# Cypress.net
KiCad netlist of a schematic drawn in Altium Designer
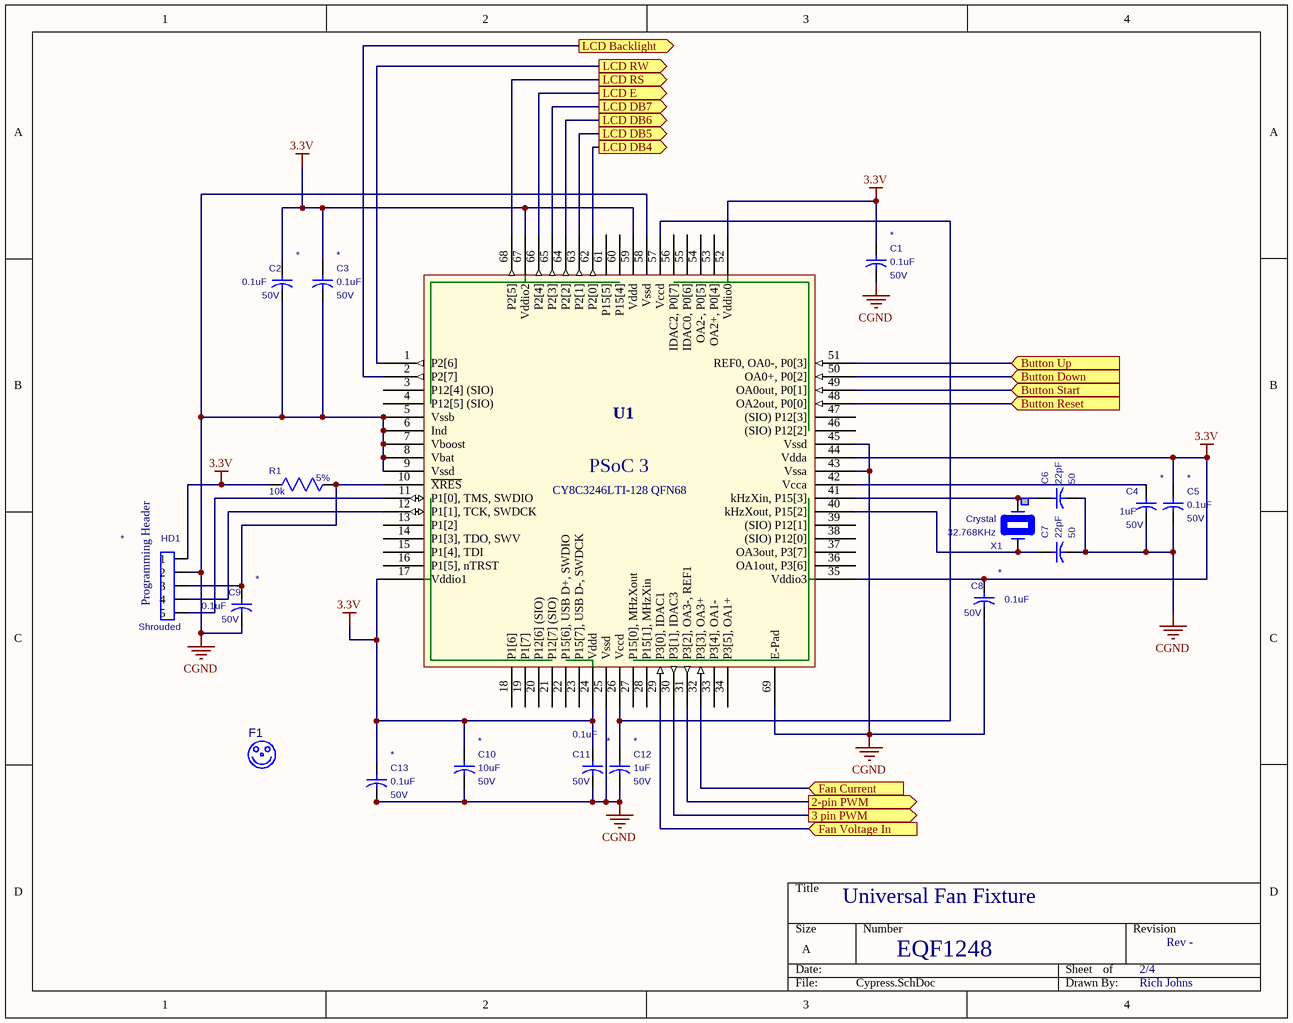
[diagram p0: Cypress.SchDoc]

(export (version "E")
  (design (tool "Eeschema 10.0.6"))
  (components
    (comp (ref "C1")
      (value "0.1uF")
      (footprint "0603")
      (fields
        (field (name "DNS") "*")
        (field (name "VOLTAGE") "50V")
        (field (name "TOLERANCE") "+/- 20%")
        (field (name "Comment") "CAP_NON_POLAR_SMT")
        (field (name "CHECKEDBY") "Sam Rhoufiry")
        (field (name "CREATEDBY") "Mike Tyger")
        (field (name "LASTUPDATEDBY") "Mike Tyger")
      )
      (libsource (lib "bome") (part "CAP_NON_POLAR_SMT"))
    )
    (comp (ref "C2")
      (value "0.1uF")
      (footprint "0603")
      (fields
        (field (name "DNS") "*")
        (field (name "VOLTAGE") "50V")
        (field (name "TOLERANCE") "+/- 20%")
        (field (name "Comment") "CAP_NON_POLAR_SMT")
        (field (name "CHECKEDBY") "Sam Rhoufiry")
        (field (name "CREATEDBY") "Mike Tyger")
        (field (name "LASTUPDATEDBY") "Mike Tyger")
      )
      (libsource (lib "bome") (part "CAP_NON_POLAR_SMT"))
    )
    (comp (ref "C3")
      (value "0.1uF")
      (footprint "0603")
      (fields
        (field (name "DNS") "*")
        (field (name "VOLTAGE") "50V")
        (field (name "TOLERANCE") "+/- 20%")
        (field (name "Comment") "CAP_NON_POLAR_SMT")
        (field (name "CHECKEDBY") "Sam Rhoufiry")
        (field (name "CREATEDBY") "Mike Tyger")
        (field (name "LASTUPDATEDBY") "Mike Tyger")
      )
      (libsource (lib "bome") (part "CAP_NON_POLAR_SMT"))
    )
    (comp (ref "C4")
      (value "1uF")
      (footprint "0603")
      (fields
        (field (name "DNS") "*")
        (field (name "VOLTAGE") "50V")
        (field (name "TOLERANCE") "+/- 20%")
        (field (name "Comment") "CAP_NON_POLAR_SMT")
        (field (name "CHECKEDBY") "Sam Rhoufiry")
        (field (name "CREATEDBY") "Mike Tyger")
        (field (name "LASTUPDATEDBY") "Mike Tyger")
      )
      (libsource (lib "bome") (part "CAP_NON_POLAR_SMT"))
    )
    (comp (ref "C5")
      (value "0.1uF")
      (footprint "0603")
      (fields
        (field (name "DNS") "*")
        (field (name "VOLTAGE") "50V")
        (field (name "TOLERANCE") "+/- 20%")
        (field (name "Comment") "CAP_NON_POLAR_SMT")
        (field (name "CHECKEDBY") "Sam Rhoufiry")
        (field (name "CREATEDBY") "Mike Tyger")
        (field (name "LASTUPDATEDBY") "Mike Tyger")
      )
      (libsource (lib "bome") (part "CAP_NON_POLAR_SMT"))
    )
    (comp (ref "C6")
      (value "22pF")
      (footprint "0603")
      (description "Capacitor, 22pF, 50, Ceramic, NPO, +/-5%, Non-Polar, 0603, 2, Kemet:C0603C220J5GACTU or equivalent")
      (fields
        (field (name "TOLERANCE") "+/-5%")
        (field (name "VOLTAGE") "50")
        (field (name "Comment") "22pF_0603")
        (field (name "CHECKEDBY") "gdeguzman")
        (field (name "LASTUPDATEDBY") "Michael Angeli")
      )
      (libsource (lib "bome") (part "22pF_0603"))
    )
    (comp (ref "C7")
      (value "22pF")
      (footprint "0603")
      (description "Capacitor, 22pF, 50, Ceramic, NPO, +/-5%, Non-Polar, 0603, 2, Kemet:C0603C220J5GACTU or equivalent")
      (fields
        (field (name "TOLERANCE") "+/-5%")
        (field (name "VOLTAGE") "50")
        (field (name "Comment") "22pF_0603")
        (field (name "CHECKEDBY") "gdeguzman")
        (field (name "LASTUPDATEDBY") "Michael Angeli")
      )
      (libsource (lib "bome") (part "22pF_0603"))
    )
    (comp (ref "C8")
      (value "0.1uF")
      (footprint "0603")
      (fields
        (field (name "DNS") "*")
        (field (name "VOLTAGE") "50V")
        (field (name "TOLERANCE") "+/- 20%")
        (field (name "Comment") "CAP_NON_POLAR_SMT")
        (field (name "CHECKEDBY") "Sam Rhoufiry")
        (field (name "CREATEDBY") "Mike Tyger")
        (field (name "LASTUPDATEDBY") "Mike Tyger")
      )
      (libsource (lib "bome") (part "CAP_NON_POLAR_SMT"))
    )
    (comp (ref "C9")
      (value "0.1uF")
      (footprint "0603")
      (fields
        (field (name "DNS") "*")
        (field (name "VOLTAGE") "50V")
        (field (name "TOLERANCE") "+/- 20%")
        (field (name "Comment") "CAP_NON_POLAR_SMT")
        (field (name "CHECKEDBY") "Sam Rhoufiry")
        (field (name "CREATEDBY") "Mike Tyger")
        (field (name "LASTUPDATEDBY") "Mike Tyger")
      )
      (libsource (lib "bome") (part "CAP_NON_POLAR_SMT"))
    )
    (comp (ref "C10")
      (value "10uF")
      (footprint "1206")
      (fields
        (field (name "DNS") "*")
        (field (name "VOLTAGE") "50V")
        (field (name "TOLERANCE") "+/- 20%")
        (field (name "Comment") "CAP_NON_POLAR_SMT")
        (field (name "CHECKEDBY") "Sam Rhoufiry")
        (field (name "CREATEDBY") "Mike Tyger")
        (field (name "LASTUPDATEDBY") "Mike Tyger")
      )
      (libsource (lib "bome") (part "CAP_NON_POLAR_SMT"))
    )
    (comp (ref "C11")
      (value "0.1uF")
      (footprint "0603")
      (fields
        (field (name "DNS") "*")
        (field (name "VOLTAGE") "50V")
        (field (name "TOLERANCE") "+/- 20%")
        (field (name "Comment") "CAP_NON_POLAR_SMT")
        (field (name "CHECKEDBY") "Sam Rhoufiry")
        (field (name "CREATEDBY") "Mike Tyger")
        (field (name "LASTUPDATEDBY") "Mike Tyger")
      )
      (libsource (lib "bome") (part "CAP_NON_POLAR_SMT"))
    )
    (comp (ref "C12")
      (value "1uF")
      (footprint "0603")
      (fields
        (field (name "DNS") "*")
        (field (name "VOLTAGE") "50V")
        (field (name "TOLERANCE") "+/- 20%")
        (field (name "Comment") "CAP_NON_POLAR_SMT")
        (field (name "CHECKEDBY") "Sam Rhoufiry")
        (field (name "CREATEDBY") "Mike Tyger")
        (field (name "LASTUPDATEDBY") "Mike Tyger")
      )
      (libsource (lib "bome") (part "CAP_NON_POLAR_SMT"))
    )
    (comp (ref "C13")
      (value "0.1uF")
      (footprint "0603")
      (fields
        (field (name "DNS") "*")
        (field (name "VOLTAGE") "50V")
        (field (name "TOLERANCE") "+/- 20%")
        (field (name "Comment") "CAP_NON_POLAR_SMT")
        (field (name "CHECKEDBY") "Sam Rhoufiry")
        (field (name "CREATEDBY") "Mike Tyger")
        (field (name "LASTUPDATEDBY") "Mike Tyger")
      )
      (libsource (lib "bome") (part "CAP_NON_POLAR_SMT"))
    )
    (comp (ref "F1")
      (value "FIDUCIAL_SMILEY")
      (footprint "FIDUCIAL_SMILEY")
      (description "Fiducial, Smiley, PCB reference point, not a component")
      (fields (field (name "CREATEDBY") "Mike Tyger") (field (name "LASTUPDATEDBY") "Michael Angeli"))
      (libsource (lib "bome") (part "FIDUCIAL_SMILEY"))
    )
    (comp (ref "HD1")
      (value "HDR5PIN100SHRD")
      (footprint "HDR5PIN100SHRD")
      (description "Header, 0.100 in., 5 pin Pins, Shrouded, AMP: 644486-5")
      (fields
        (field (name "DNS") "*")
        (field (name "HEADERTYPE") "Shrouded")
        (field (name "CHECKEDBY") "Michael Angeli")
      )
      (libsource (lib "bome") (part "HDR5PIN100SHRD"))
    )
    (comp (ref "R1")
      (value "10k")
      (footprint "RC0603REFLOW-IPC")
      (description "Resistor, 18, ThickFilm, 5%, 0603, 1/8W, Any")
      (fields
        (field (name "TOLERANCE") "5%")
        (field (name "Comment") "R0603REFLOW_5%_1/8WATT")
        (field (name "CHECKEDBY") "*")
      )
      (libsource (lib "bome") (part "R0603REFLOW_5%_1/8WATT"))
    )
    (comp (ref "U1")
      (value "CY8C3246LTI-128 QFN68")
      (footprint "PSoC 3 and 5LP:QFN68_8x8-MD")
      (description "CY8C3xxxLTx-xxx 68 pin QFN")
      (fields (field (name "MFG") "Cypress"))
      (libsource (lib "PSoC 3") (part "CY8C3xxxLTx-xxx QFN68"))
    )
    (comp (ref "X1")
      (value "32.768KHZ_CRYSTAL")
      (footprint ".03_Small_Footprint_CRYSTAL")
      (description "Xtal, 0.7 mm, Cylinder, 2, Crystal, 32.768KHz, ECS: ECS-.327-12.5-13;Alternates require approval")
      (fields
        (field (name "FREQUENCY") "32.768KHz")
        (field (name "XTALTYPE") "Crystal")
        (field (name "CHECKEDBY") "Sam Rhoufiry")
      )
      (libsource (lib "bome") (part "32.768KHZ_CRYSTAL"))
    )
  )
  (nets
    (net (code "1") (name "/2-pin PWM") (class "Default")
      (node (ref "U1") (pin "31") (pinfunction "P3[2],_OA3-,_REF1_31") (pintype "output"))
    )
    (net (code "2") (name "/3 pin PWM") (class "Default")
      (node (ref "U1") (pin "30") (pinfunction "P3[1],_IDAC3_30") (pintype "output"))
    )
    (net (code "3") (name "/Button Down") (class "Default")
      (node (ref "U1") (pin "50") (pinfunction "OA0+,_P0[2]_50") (pintype "input"))
    )
    (net (code "4") (name "/Button Reset") (class "Default")
      (node (ref "U1") (pin "48") (pinfunction "OA2out,_P0[0]_48") (pintype "input"))
    )
    (net (code "5") (name "/Button Start") (class "Default")
      (node (ref "U1") (pin "49") (pinfunction "OA0out,_P0[1]_49") (pintype "input"))
    )
    (net (code "6") (name "/Button Up") (class "Default")
      (node (ref "U1") (pin "51") (pinfunction "REF0,_OA0-,_P0[3]_51") (pintype "input"))
    )
    (net (code "7") (name "/Fan Current") (class "Default")
      (node (ref "U1") (pin "32") (pinfunction "P3[3],_OA3+_32") (pintype "input"))
    )
    (net (code "8") (name "/Fan Voltage In") (class "Default")
      (node (ref "U1") (pin "29") (pinfunction "P3[0],_IDAC1_29") (pintype "input"))
    )
    (net (code "9") (name "/LCD Backlight") (class "Default")
      (node (ref "U1") (pin "2") (pinfunction "P2[7]_2") (pintype "output"))
    )
    (net (code "10") (name "/LCD DB4") (class "Default")
      (node (ref "U1") (pin "62") (pinfunction "P2[0]_62") (pintype "output"))
    )
    (net (code "11") (name "/LCD DB5") (class "Default")
      (node (ref "U1") (pin "63") (pinfunction "P2[1]_63") (pintype "output"))
    )
    (net (code "12") (name "/LCD DB6") (class "Default")
      (node (ref "U1") (pin "64") (pinfunction "P2[2]_64") (pintype "output"))
    )
    (net (code "13") (name "/LCD DB7") (class "Default")
      (node (ref "U1") (pin "65") (pinfunction "P2[3]_65") (pintype "output"))
    )
    (net (code "14") (name "/LCD E") (class "Default")
      (node (ref "U1") (pin "66") (pinfunction "P2[4]_66") (pintype "output"))
    )
    (net (code "15") (name "/LCD RS") (class "Default")
      (node (ref "U1") (pin "68") (pinfunction "P2[5]_68") (pintype "output"))
    )
    (net (code "16") (name "/LCD RW") (class "Default")
      (node (ref "U1") (pin "1") (pinfunction "P2[6]_1") (pintype "output"))
    )
    (net (code "17") (name "3.3V") (class "Default")
      (node (ref "C1") (pin "1") (pinfunction "pin1_1") (pintype "passive"))
      (node (ref "C10") (pin "1") (pinfunction "pin1_1") (pintype "passive"))
      (node (ref "C11") (pin "1") (pinfunction "pin1_1") (pintype "passive"))
      (node (ref "C13") (pin "1") (pinfunction "pin1_1") (pintype "passive"))
      (node (ref "C2") (pin "1") (pinfunction "pin1_1") (pintype "passive"))
      (node (ref "C3") (pin "1") (pinfunction "pin1_1") (pintype "passive"))
      (node (ref "C5") (pin "1") (pinfunction "pin1_1") (pintype "passive"))
      (node (ref "C8") (pin "1") (pinfunction "pin1_1") (pintype "passive"))
      (node (ref "HD1") (pin "1") (pinfunction "1_1") (pintype "passive"))
      (node (ref "R1") (pin "2") (pinfunction "pin2_2") (pintype "passive"))
      (node (ref "U1") (pin "17") (pinfunction "Vddio1_17") (pintype "power_in"))
      (node (ref "U1") (pin "24") (pinfunction "Vddd_24") (pintype "power_in"))
      (node (ref "U1") (pin "35") (pinfunction "Vddio3_35") (pintype "power_in"))
      (node (ref "U1") (pin "44") (pinfunction "Vdda_44") (pintype "power_in"))
      (node (ref "U1") (pin "52") (pinfunction "Vddio0_52") (pintype "power_in"))
      (node (ref "U1") (pin "59") (pinfunction "Vddd_59") (pintype "power_in"))
      (node (ref "U1") (pin "67") (pinfunction "Vddio2_67") (pintype "power_in"))
    )
    (net (code "18") (name "CGND") (class "Default")
      (node (ref "C1") (pin "2") (pinfunction "pin2_2") (pintype "passive"))
      (node (ref "C10") (pin "2") (pinfunction "pin2_2") (pintype "passive"))
      (node (ref "C11") (pin "2") (pinfunction "pin2_2") (pintype "passive"))
      (node (ref "C12") (pin "2") (pinfunction "pin2_2") (pintype "passive"))
      (node (ref "C13") (pin "2") (pinfunction "pin2_2") (pintype "passive"))
      (node (ref "C2") (pin "2") (pinfunction "pin2_2") (pintype "passive"))
      (node (ref "C3") (pin "2") (pinfunction "pin2_2") (pintype "passive"))
      (node (ref "C4") (pin "2") (pinfunction "pin2_2") (pintype "passive"))
      (node (ref "C5") (pin "2") (pinfunction "pin2_2") (pintype "passive"))
      (node (ref "C6") (pin "2") (pinfunction "pin2_2") (pintype "passive"))
      (node (ref "C7") (pin "2") (pinfunction "pin2_2") (pintype "passive"))
      (node (ref "C8") (pin "2") (pinfunction "pin2_2") (pintype "passive"))
      (node (ref "C9") (pin "2") (pinfunction "pin2_2") (pintype "passive"))
      (node (ref "HD1") (pin "2") (pinfunction "2_2") (pintype "passive"))
      (node (ref "U1") (pin "25") (pinfunction "Vssd_25") (pintype "power_in"))
      (node (ref "U1") (pin "43") (pinfunction "Vssa_43") (pintype "passive"))
      (node (ref "U1") (pin "45") (pinfunction "Vssd_45") (pintype "passive"))
      (node (ref "U1") (pin "5") (pinfunction "Vssb_5") (pintype "power_in"))
      (node (ref "U1") (pin "58") (pinfunction "Vssd_58") (pintype "power_in"))
      (node (ref "U1") (pin "6") (pinfunction "Ind_6") (pintype "passive"))
      (node (ref "U1") (pin "69") (pinfunction "E-Pad_69") (pintype "power_in"))
      (node (ref "U1") (pin "7") (pinfunction "Vboost_7") (pintype "passive"))
      (node (ref "U1") (pin "8") (pinfunction "Vbat_8") (pintype "power_in"))
      (node (ref "U1") (pin "9") (pinfunction "Vssd_9") (pintype "power_in"))
    )
    (net (code "19") (name "Net-(C4-pin1)") (class "Default")
      (node (ref "C4") (pin "1") (pinfunction "pin1_1") (pintype "passive"))
      (node (ref "U1") (pin "42") (pinfunction "Vcca_42") (pintype "power_in"))
    )
    (net (code "20") (name "Net-(C6-pin1)") (class "Default")
      (node (ref "C6") (pin "1") (pinfunction "pin1_1") (pintype "passive"))
      (node (ref "U1") (pin "41") (pinfunction "kHzXin,_P15[3]_41") (pintype "passive"))
      (node (ref "X1") (pin "1") (pinfunction "1_1") (pintype "passive"))
    )
    (net (code "21") (name "Net-(C7-pin1)") (class "Default")
      (node (ref "C7") (pin "1") (pinfunction "pin1_1") (pintype "passive"))
      (node (ref "U1") (pin "40") (pinfunction "kHzXout,_P15[2]_40") (pintype "passive"))
      (node (ref "X1") (pin "2") (pinfunction "2_2") (pintype "passive"))
    )
    (net (code "22") (name "Net-(C9-pin1)") (class "Default")
      (node (ref "C9") (pin "1") (pinfunction "pin1_1") (pintype "passive"))
      (node (ref "HD1") (pin "3") (pinfunction "3_3") (pintype "passive"))
      (node (ref "R1") (pin "1") (pinfunction "pin1_1") (pintype "passive"))
      (node (ref "U1") (pin "10") (pinfunction "~{XRES}_10") (pintype "tri_state"))
    )
    (net (code "23") (name "Net-(C12-pin1)") (class "Default")
      (node (ref "C12") (pin "1") (pinfunction "pin1_1") (pintype "passive"))
      (node (ref "U1") (pin "26") (pinfunction "Vccd_26") (pintype "power_in"))
      (node (ref "U1") (pin "57") (pinfunction "Vccd_57") (pintype "power_in"))
    )
    (net (code "24") (name "Net-(U1-P1[0],_TMS,_SWDIO)") (class "Default")
      (node (ref "HD1") (pin "5") (pinfunction "5_5") (pintype "passive"))
      (node (ref "U1") (pin "11") (pinfunction "P1[0],_TMS,_SWDIO_11") (pintype "bidirectional"))
    )
    (net (code "25") (name "Net-(U1-P1[1],_TCK,_SWDCK)") (class "Default")
      (node (ref "HD1") (pin "4") (pinfunction "4_4") (pintype "passive"))
      (node (ref "U1") (pin "12") (pinfunction "P1[1],_TCK,_SWDCK_12") (pintype "bidirectional"))
    )
    (net (code "26") (name "unconnected-(HD1-Pad6)") (class "Default")
      (node (ref "HD1") (pin "6") (pintype "passive"))
    )
    (net (code "27") (name "unconnected-(U1-(SIO)_P12[0]-Pad38)") (class "Default")
      (node (ref "U1") (pin "38") (pinfunction "(SIO)_P12[0]_38") (pintype "passive"))
    )
    (net (code "28") (name "unconnected-(U1-(SIO)_P12[1]-Pad39)") (class "Default")
      (node (ref "U1") (pin "39") (pinfunction "(SIO)_P12[1]_39") (pintype "passive"))
    )
    (net (code "29") (name "unconnected-(U1-(SIO)_P12[2]-Pad46)") (class "Default")
      (node (ref "U1") (pin "46") (pinfunction "(SIO)_P12[2]_46") (pintype "passive"))
    )
    (net (code "30") (name "unconnected-(U1-(SIO)_P12[3]-Pad47)") (class "Default")
      (node (ref "U1") (pin "47") (pinfunction "(SIO)_P12[3]_47") (pintype "passive"))
    )
    (net (code "31") (name "unconnected-(U1-IDAC0,_P0[6]-Pad55)") (class "Default")
      (node (ref "U1") (pin "55") (pinfunction "IDAC0,_P0[6]_55") (pintype "passive"))
    )
    (net (code "32") (name "unconnected-(U1-IDAC2,_P0[7]-Pad56)") (class "Default")
      (node (ref "U1") (pin "56") (pinfunction "IDAC2,_P0[7]_56") (pintype "passive"))
    )
    (net (code "33") (name "unconnected-(U1-OA1out,_P3[6]-Pad36)") (class "Default")
      (node (ref "U1") (pin "36") (pinfunction "OA1out,_P3[6]_36") (pintype "passive"))
    )
    (net (code "34") (name "unconnected-(U1-OA2+,_P0[4]-Pad53)") (class "Default")
      (node (ref "U1") (pin "53") (pinfunction "OA2+,_P0[4]_53") (pintype "passive"))
    )
    (net (code "35") (name "unconnected-(U1-OA2-,_P0[5]-Pad54)") (class "Default")
      (node (ref "U1") (pin "54") (pinfunction "OA2-,_P0[5]_54") (pintype "passive"))
    )
    (net (code "36") (name "unconnected-(U1-OA3out,_P3[7]-Pad37)") (class "Default")
      (node (ref "U1") (pin "37") (pinfunction "OA3out,_P3[7]_37") (pintype "passive"))
    )
    (net (code "37") (name "unconnected-(U1-P1[2]-Pad13)") (class "Default")
      (node (ref "U1") (pin "13") (pinfunction "P1[2]_13") (pintype "passive"))
    )
    (net (code "38") (name "unconnected-(U1-P1[3],_TDO,_SWV-Pad14)") (class "Default")
      (node (ref "U1") (pin "14") (pinfunction "P1[3],_TDO,_SWV_14") (pintype "passive"))
    )
    (net (code "39") (name "unconnected-(U1-P1[4],_TDI-Pad15)") (class "Default")
      (node (ref "U1") (pin "15") (pinfunction "P1[4],_TDI_15") (pintype "passive"))
    )
    (net (code "40") (name "unconnected-(U1-P1[5],_nTRST-Pad16)") (class "Default")
      (node (ref "U1") (pin "16") (pinfunction "P1[5],_nTRST_16") (pintype "passive"))
    )
    (net (code "41") (name "unconnected-(U1-P1[6]-Pad18)") (class "Default")
      (node (ref "U1") (pin "18") (pinfunction "P1[6]_18") (pintype "passive"))
    )
    (net (code "42") (name "unconnected-(U1-P1[7]-Pad19)") (class "Default")
      (node (ref "U1") (pin "19") (pinfunction "P1[7]_19") (pintype "passive"))
    )
    (net (code "43") (name "unconnected-(U1-P3[4],_OA1--Pad33)") (class "Default")
      (node (ref "U1") (pin "33") (pinfunction "P3[4],_OA1-_33") (pintype "passive"))
    )
    (net (code "44") (name "unconnected-(U1-P3[5],_OA1+-Pad34)") (class "Default")
      (node (ref "U1") (pin "34") (pinfunction "P3[5],_OA1+_34") (pintype "passive"))
    )
    (net (code "45") (name "unconnected-(U1-P12[4]_(SIO)-Pad3)") (class "Default")
      (node (ref "U1") (pin "3") (pinfunction "P12[4]_(SIO)_3") (pintype "passive"))
    )
    (net (code "46") (name "unconnected-(U1-P12[5]_(SIO)-Pad4)") (class "Default")
      (node (ref "U1") (pin "4") (pinfunction "P12[5]_(SIO)_4") (pintype "passive"))
    )
    (net (code "47") (name "unconnected-(U1-P12[6]_(SIO)-Pad20)") (class "Default")
      (node (ref "U1") (pin "20") (pinfunction "P12[6]_(SIO)_20") (pintype "passive"))
    )
    (net (code "48") (name "unconnected-(U1-P12[7]_(SIO)-Pad21)") (class "Default")
      (node (ref "U1") (pin "21") (pinfunction "P12[7]_(SIO)_21") (pintype "passive"))
    )
    (net (code "49") (name "unconnected-(U1-P15[0],_MHzXout-Pad27)") (class "Default")
      (node (ref "U1") (pin "27") (pinfunction "P15[0],_MHzXout_27") (pintype "passive"))
    )
    (net (code "50") (name "unconnected-(U1-P15[1],_MHzXin-Pad28)") (class "Default")
      (node (ref "U1") (pin "28") (pinfunction "P15[1],_MHzXin_28") (pintype "passive"))
    )
    (net (code "51") (name "unconnected-(U1-P15[4]-Pad60)") (class "Default")
      (node (ref "U1") (pin "60") (pinfunction "P15[4]_60") (pintype "passive"))
    )
    (net (code "52") (name "unconnected-(U1-P15[5]-Pad61)") (class "Default")
      (node (ref "U1") (pin "61") (pinfunction "P15[5]_61") (pintype "passive"))
    )
    (net (code "53") (name "unconnected-(U1-P15[6],_USB_D+,_SWDIO-Pad22)") (class "Default")
      (node (ref "U1") (pin "22") (pinfunction "P15[6],_USB_D+,_SWDIO_22") (pintype "passive"))
    )
    (net (code "54") (name "unconnected-(U1-P15[7],_USB_D-,_SWDCK-Pad23)") (class "Default")
      (node (ref "U1") (pin "23") (pinfunction "P15[7],_USB_D-,_SWDCK_23") (pintype "passive"))
    )
  )
)
